# armor_schematic_std_single.net
KiCad netlist of a schematic drawn in EasyEDA
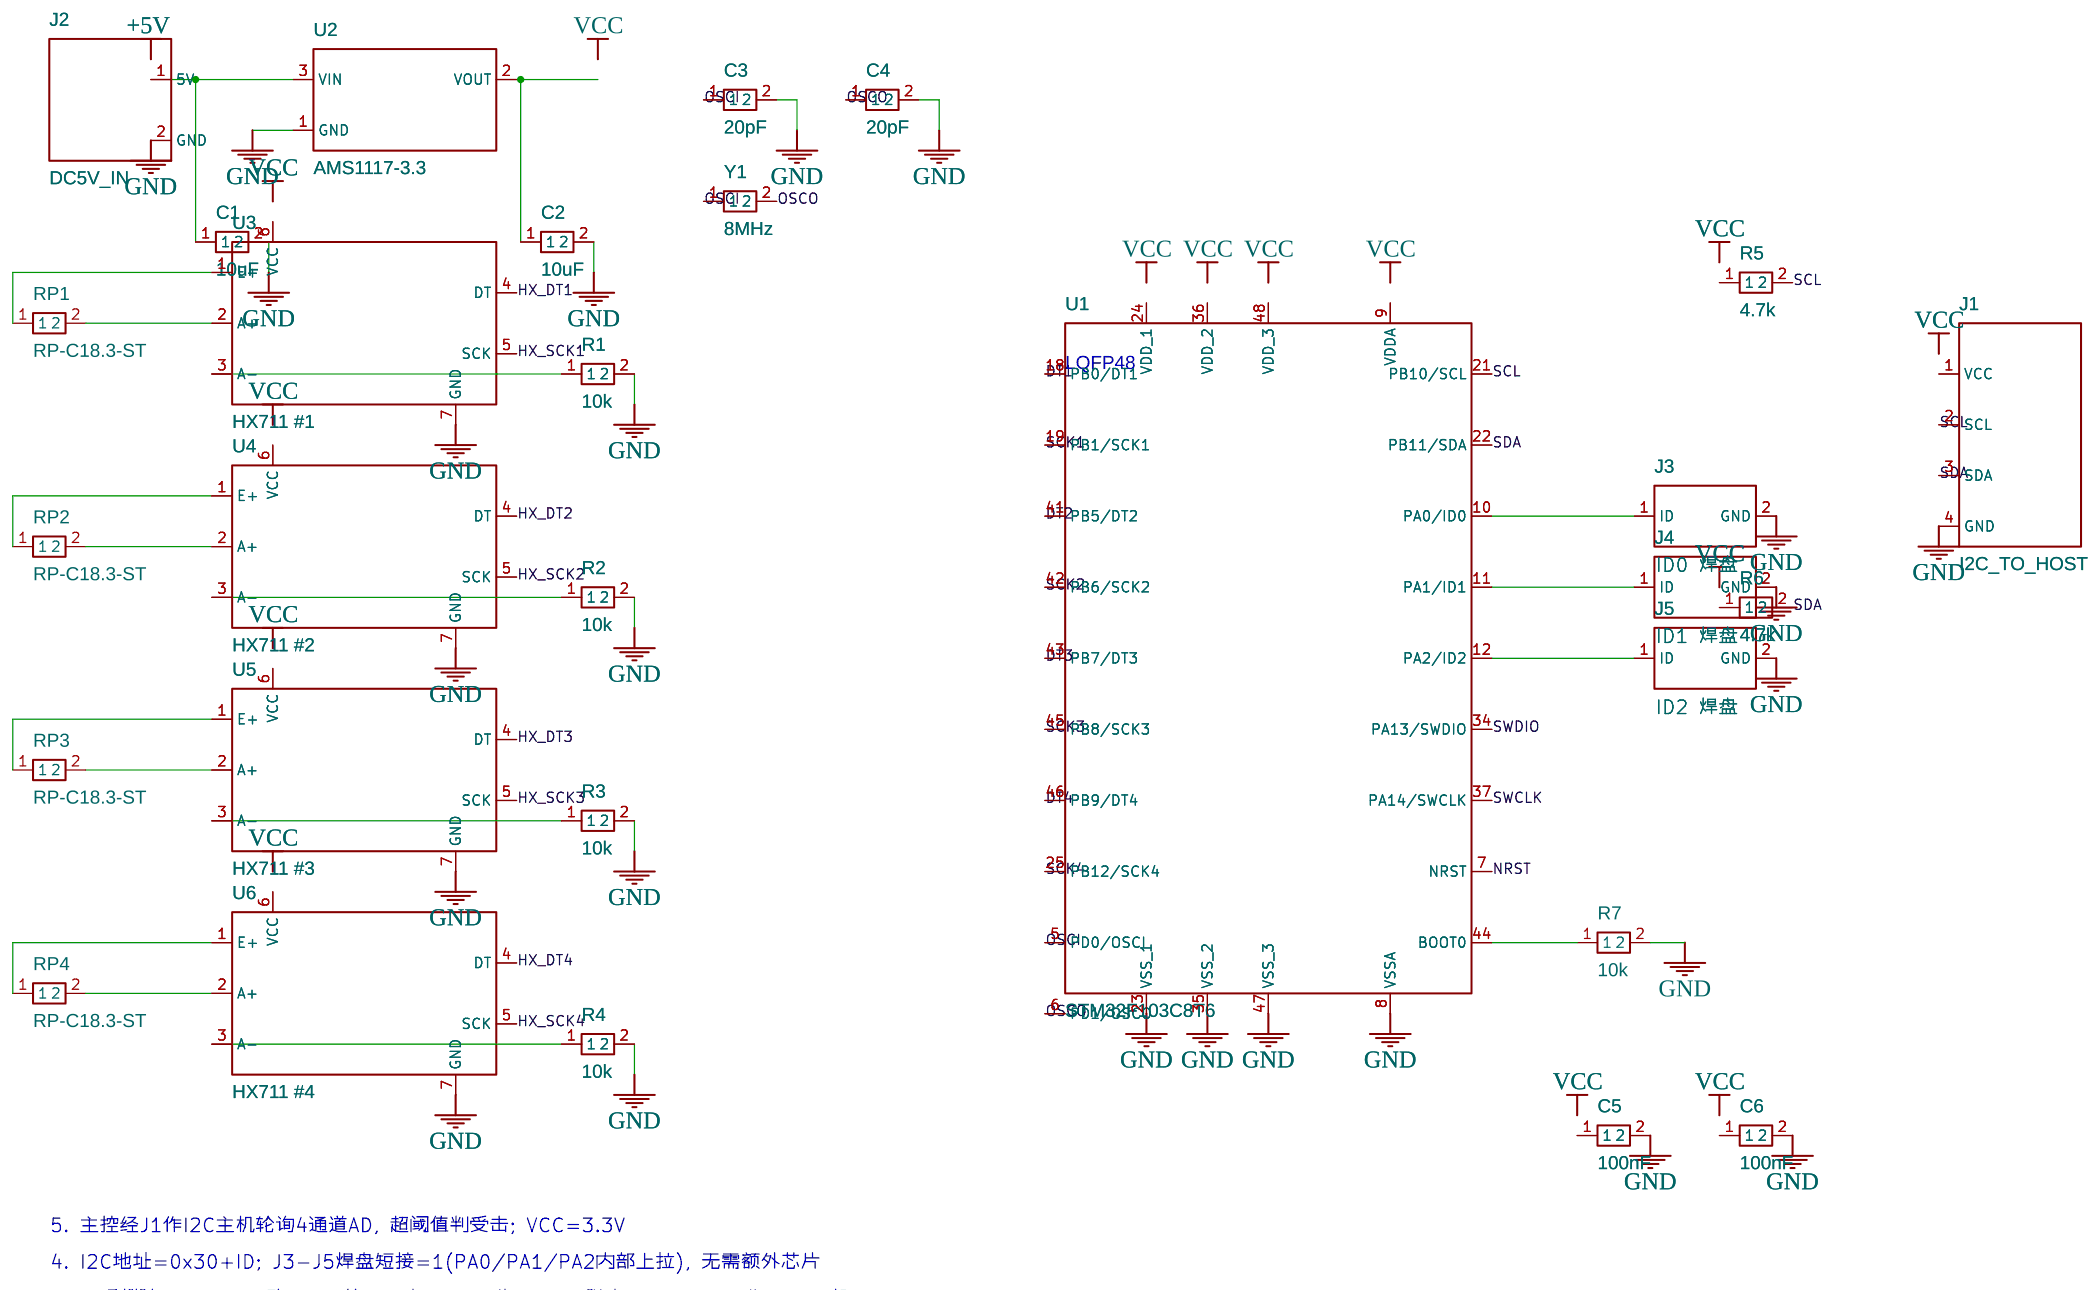
[diagram p0: schematic sheet]

(export (version "E")
  (design (tool "Eeschema 10.0.6"))
  (components
    (comp (ref "C1")
      (value "10uF")
      (fields (field (name "BOM_Manufacturer Part") "CL21A106KAYNNNE"))
      (libsource (lib "") (part "10uF"))
    )
    (comp (ref "C2")
      (value "10uF")
      (fields (field (name "BOM_Manufacturer Part") "CL21A106KAYNNNE"))
      (libsource (lib "") (part "10uF"))
    )
    (comp (ref "C3")
      (value "20pF")
      (fields (field (name "BOM_Manufacturer Part") "CL10C200JB8NNNC"))
      (libsource (lib "") (part "20pF"))
    )
    (comp (ref "C4")
      (value "20pF")
      (fields (field (name "BOM_Manufacturer Part") "CL10C200JB8NNNC"))
      (libsource (lib "") (part "20pF"))
    )
    (comp (ref "C5")
      (value "100nF")
      (fields (field (name "BOM_Manufacturer Part") "CC0603KRX7R9BB104"))
      (libsource (lib "") (part "100nF"))
    )
    (comp (ref "C6")
      (value "100nF")
      (fields (field (name "BOM_Manufacturer Part") "CC0603KRX7R9BB104"))
      (libsource (lib "") (part "100nF"))
    )
    (comp (ref "J1")
      (value "I2C_TO_HOST")
      (fields (field (name "BOM_Manufacturer Part") "PZ254V-11-04P"))
      (libsource (lib "") (part "I2C_TO_HOST"))
    )
    (comp (ref "J2")
      (value "DC5V_IN")
      (fields (field (name "BOM_Manufacturer Part") "PZ254V-11-02P"))
      (libsource (lib "") (part "DC5V_IN"))
    )
    (comp (ref "J3")
      (value "ID0 焊盘")
      (fields (field (name "BOM_Manufacturer Part") "PZ254V-11-02P"))
      (libsource (lib "") (part "ID0 焊盘"))
    )
    (comp (ref "J4")
      (value "ID1 焊盘")
      (fields (field (name "BOM_Manufacturer Part") "PZ254V-11-02P"))
      (libsource (lib "") (part "ID1 焊盘"))
    )
    (comp (ref "J5")
      (value "ID2 焊盘")
      (fields (field (name "BOM_Manufacturer Part") "PZ254V-11-02P"))
      (libsource (lib "") (part "ID2 焊盘"))
    )
    (comp (ref "R1")
      (value "10k")
      (fields (field (name "BOM_Manufacturer Part") "0603WAF1002T5E"))
      (libsource (lib "") (part "10k"))
    )
    (comp (ref "R2")
      (value "10k")
      (fields (field (name "BOM_Manufacturer Part") "0603WAF1002T5E"))
      (libsource (lib "") (part "10k"))
    )
    (comp (ref "R3")
      (value "10k")
      (fields (field (name "BOM_Manufacturer Part") "0603WAF1002T5E"))
      (libsource (lib "") (part "10k"))
    )
    (comp (ref "R4")
      (value "10k")
      (fields (field (name "BOM_Manufacturer Part") "0603WAF1002T5E"))
      (libsource (lib "") (part "10k"))
    )
    (comp (ref "R5")
      (value "4.7k")
      (fields (field (name "BOM_Manufacturer Part") "0603WAF4701T5E"))
      (libsource (lib "") (part "4.7k"))
    )
    (comp (ref "R6")
      (value "4.7k")
      (fields (field (name "BOM_Manufacturer Part") "0603WAF4701T5E"))
      (libsource (lib "") (part "4.7k"))
    )
    (comp (ref "R7")
      (value "10k")
      (fields (field (name "BOM_Manufacturer Part") "0603WAF1002T5E"))
      (libsource (lib "") (part "10k"))
    )
    (comp (ref "RP1") (value "RP-C18.3-ST") (libsource (lib "") (part "RP-C18.3-ST")))
    (comp (ref "RP2") (value "RP-C18.3-ST") (libsource (lib "") (part "RP-C18.3-ST")))
    (comp (ref "RP3") (value "RP-C18.3-ST") (libsource (lib "") (part "RP-C18.3-ST")))
    (comp (ref "RP4") (value "RP-C18.3-ST") (libsource (lib "") (part "RP-C18.3-ST")))
    (comp (ref "U1") (value "STM32F103C8T6") (libsource (lib "") (part "STM32F103C8T6")))
    (comp (ref "U2") (value "AMS1117-3.3") (libsource (lib "") (part "AMS1117-3.3")))
    (comp (ref "U3")
      (value "HX711 #1")
      (fields (field (name "BOM_Manufacturer Part") "HX711 module"))
      (libsource (lib "") (part "HX711 #1"))
    )
    (comp (ref "U4")
      (value "HX711 #2")
      (fields (field (name "BOM_Manufacturer Part") "HX711 module"))
      (libsource (lib "") (part "HX711 #2"))
    )
    (comp (ref "U5")
      (value "HX711 #3")
      (fields (field (name "BOM_Manufacturer Part") "HX711 module"))
      (libsource (lib "") (part "HX711 #3"))
    )
    (comp (ref "U6")
      (value "HX711 #4")
      (fields (field (name "BOM_Manufacturer Part") "HX711 module"))
      (libsource (lib "") (part "HX711 #4"))
    )
    (comp (ref "Y1")
      (value "8MHz")
      (fields (field (name "BOM_Manufacturer Part") "7U08000E10UCG"))
      (libsource (lib "") (part "8MHz"))
    )
  )
  (nets
    (net (code "2") (name "/DT1") (class "Default")
      (node (ref "U1") (pin "18") (pinfunction "PB0/DT1_18") (pintype "unspecified"))
    )
    (net (code "3") (name "/DT2") (class "Default")
      (node (ref "U1") (pin "41") (pinfunction "PB5/DT2_41") (pintype "unspecified"))
    )
    (net (code "4") (name "/DT3") (class "Default")
      (node (ref "U1") (pin "43") (pinfunction "PB7/DT3_43") (pintype "unspecified"))
    )
    (net (code "5") (name "/DT4") (class "Default")
      (node (ref "U1") (pin "46") (pinfunction "PB9/DT4_46") (pintype "unspecified"))
    )
    (net (code "6") (name "/HX_DT1") (class "Default")
      (node (ref "U3") (pin "4") (pinfunction "DT_4") (pintype "unspecified"))
    )
    (net (code "7") (name "/HX_DT2") (class "Default")
      (node (ref "U4") (pin "4") (pinfunction "DT_4") (pintype "unspecified"))
    )
    (net (code "8") (name "/HX_DT3") (class "Default")
      (node (ref "U5") (pin "4") (pinfunction "DT_4") (pintype "unspecified"))
    )
    (net (code "9") (name "/HX_DT4") (class "Default")
      (node (ref "U6") (pin "4") (pinfunction "DT_4") (pintype "unspecified"))
    )
    (net (code "10") (name "/HX_SCK1") (class "Default")
      (node (ref "U3") (pin "5") (pinfunction "SCK_5") (pintype "unspecified"))
    )
    (net (code "11") (name "/HX_SCK2") (class "Default")
      (node (ref "U4") (pin "5") (pinfunction "SCK_5") (pintype "unspecified"))
    )
    (net (code "12") (name "/HX_SCK3") (class "Default")
      (node (ref "U5") (pin "5") (pinfunction "SCK_5") (pintype "unspecified"))
    )
    (net (code "13") (name "/HX_SCK4") (class "Default")
      (node (ref "U6") (pin "5") (pinfunction "SCK_5") (pintype "unspecified"))
    )
    (net (code "14") (name "/NRST") (class "Default")
      (node (ref "U1") (pin "7") (pinfunction "NRST_7") (pintype "unspecified"))
    )
    (net (code "15") (name "/OSCI") (class "Default")
      (node (ref "C3") (pin "1") (pinfunction "1_1") (pintype "unspecified"))
      (node (ref "U1") (pin "5") (pinfunction "PD0/OSCI_5") (pintype "unspecified"))
      (node (ref "Y1") (pin "1") (pinfunction "1_1") (pintype "unspecified"))
    )
    (net (code "16") (name "/OSCO") (class "Default")
      (node (ref "C4") (pin "1") (pinfunction "1_1") (pintype "unspecified"))
      (node (ref "U1") (pin "6") (pinfunction "PD1/OSCO_6") (pintype "unspecified"))
      (node (ref "Y1") (pin "2") (pinfunction "2_2") (pintype "unspecified"))
    )
    (net (code "17") (name "/SCK1") (class "Default")
      (node (ref "U1") (pin "19") (pinfunction "PB1/SCK1_19") (pintype "unspecified"))
    )
    (net (code "18") (name "/SCK2") (class "Default")
      (node (ref "U1") (pin "42") (pinfunction "PB6/SCK2_42") (pintype "unspecified"))
    )
    (net (code "19") (name "/SCK3") (class "Default")
      (node (ref "U1") (pin "45") (pinfunction "PB8/SCK3_45") (pintype "unspecified"))
    )
    (net (code "20") (name "/SCK4") (class "Default")
      (node (ref "U1") (pin "25") (pinfunction "PB12/SCK4_25") (pintype "unspecified"))
    )
    (net (code "21") (name "/SCL") (class "Default")
      (node (ref "J1") (pin "2") (pinfunction "SCL_2") (pintype "unspecified"))
      (node (ref "R5") (pin "2") (pinfunction "2_2") (pintype "unspecified"))
      (node (ref "U1") (pin "21") (pinfunction "PB10/SCL_21") (pintype "unspecified"))
    )
    (net (code "22") (name "/SDA") (class "Default")
      (node (ref "J1") (pin "3") (pinfunction "SDA_3") (pintype "unspecified"))
      (node (ref "R6") (pin "2") (pinfunction "2_2") (pintype "unspecified"))
      (node (ref "U1") (pin "22") (pinfunction "PB11/SDA_22") (pintype "unspecified"))
    )
    (net (code "23") (name "/SWCLK") (class "Default")
      (node (ref "U1") (pin "37") (pinfunction "PA14/SWCLK_37") (pintype "unspecified"))
    )
    (net (code "24") (name "/SWDIO") (class "Default")
      (node (ref "U1") (pin "34") (pinfunction "PA13/SWDIO_34") (pintype "unspecified"))
    )
    (net (code "25") (name "GND") (class "Default")
      (node (ref "C1") (pin "2") (pinfunction "2_2") (pintype "unspecified"))
      (node (ref "C2") (pin "2") (pinfunction "2_2") (pintype "unspecified"))
      (node (ref "C3") (pin "2") (pinfunction "2_2") (pintype "unspecified"))
      (node (ref "C4") (pin "2") (pinfunction "2_2") (pintype "unspecified"))
      (node (ref "C5") (pin "2") (pinfunction "2_2") (pintype "unspecified"))
      (node (ref "C6") (pin "2") (pinfunction "2_2") (pintype "unspecified"))
      (node (ref "J1") (pin "4") (pinfunction "GND_4") (pintype "unspecified"))
      (node (ref "J2") (pin "2") (pinfunction "GND_2") (pintype "unspecified"))
      (node (ref "J3") (pin "2") (pinfunction "GND_2") (pintype "unspecified"))
      (node (ref "J4") (pin "2") (pinfunction "GND_2") (pintype "unspecified"))
      (node (ref "J5") (pin "2") (pinfunction "GND_2") (pintype "unspecified"))
      (node (ref "R1") (pin "2") (pinfunction "2_2") (pintype "unspecified"))
      (node (ref "R2") (pin "2") (pinfunction "2_2") (pintype "unspecified"))
      (node (ref "R3") (pin "2") (pinfunction "2_2") (pintype "unspecified"))
      (node (ref "R4") (pin "2") (pinfunction "2_2") (pintype "unspecified"))
      (node (ref "R7") (pin "2") (pinfunction "2_2") (pintype "unspecified"))
      (node (ref "U1") (pin "23") (pinfunction "VSS_1_23") (pintype "unspecified"))
      (node (ref "U1") (pin "35") (pinfunction "VSS_2_35") (pintype "unspecified"))
      (node (ref "U1") (pin "47") (pinfunction "VSS_3_47") (pintype "unspecified"))
      (node (ref "U1") (pin "8") (pinfunction "VSSA_8") (pintype "unspecified"))
      (node (ref "U2") (pin "1") (pinfunction "GND_1") (pintype "unspecified"))
      (node (ref "U3") (pin "7") (pinfunction "GND_7") (pintype "unspecified"))
      (node (ref "U4") (pin "7") (pinfunction "GND_7") (pintype "unspecified"))
      (node (ref "U5") (pin "7") (pinfunction "GND_7") (pintype "unspecified"))
      (node (ref "U6") (pin "7") (pinfunction "GND_7") (pintype "unspecified"))
    )
    (net (code "26") (name "Net-(J2-5V)") (class "Default")
      (node (ref "C1") (pin "1") (pinfunction "1_1") (pintype "unspecified"))
      (node (ref "J2") (pin "1") (pinfunction "5V_1") (pintype "unspecified"))
      (node (ref "U2") (pin "3") (pinfunction "VIN_3") (pintype "unspecified"))
    )
    (net (code "27") (name "Net-(J3-ID)") (class "Default")
      (node (ref "J3") (pin "1") (pinfunction "ID_1") (pintype "unspecified"))
      (node (ref "U1") (pin "10") (pinfunction "PA0/ID0_10") (pintype "unspecified"))
    )
    (net (code "28") (name "Net-(J4-ID)") (class "Default")
      (node (ref "J4") (pin "1") (pinfunction "ID_1") (pintype "unspecified"))
      (node (ref "U1") (pin "11") (pinfunction "PA1/ID1_11") (pintype "unspecified"))
    )
    (net (code "29") (name "Net-(J5-ID)") (class "Default")
      (node (ref "J5") (pin "1") (pinfunction "ID_1") (pintype "unspecified"))
      (node (ref "U1") (pin "12") (pinfunction "PA2/ID2_12") (pintype "unspecified"))
    )
    (net (code "30") (name "Net-(U1-BOOT0)") (class "Default")
      (node (ref "R7") (pin "1") (pinfunction "1_1") (pintype "unspecified"))
      (node (ref "U1") (pin "44") (pinfunction "BOOT0_44") (pintype "unspecified"))
    )
    (net (code "31") (name "Net-(U2-VOUT)") (class "Default")
      (node (ref "C2") (pin "1") (pinfunction "1_1") (pintype "unspecified"))
      (node (ref "U2") (pin "2") (pinfunction "VOUT_2") (pintype "unspecified"))
    )
    (net (code "32") (name "Net-(U3-A+)") (class "Default")
      (node (ref "RP1") (pin "2") (pinfunction "2_2") (pintype "unspecified"))
      (node (ref "U3") (pin "2") (pinfunction "A+_2") (pintype "unspecified"))
    )
    (net (code "33") (name "Net-(U3-A-)") (class "Default")
      (node (ref "R1") (pin "1") (pinfunction "1_1") (pintype "unspecified"))
      (node (ref "U3") (pin "3") (pinfunction "A-_3") (pintype "unspecified"))
    )
    (net (code "34") (name "Net-(U3-E+)") (class "Default")
      (node (ref "RP1") (pin "1") (pinfunction "1_1") (pintype "unspecified"))
      (node (ref "U3") (pin "1") (pinfunction "E+_1") (pintype "unspecified"))
    )
    (net (code "35") (name "Net-(U4-A+)") (class "Default")
      (node (ref "RP2") (pin "2") (pinfunction "2_2") (pintype "unspecified"))
      (node (ref "U4") (pin "2") (pinfunction "A+_2") (pintype "unspecified"))
    )
    (net (code "36") (name "Net-(U4-A-)") (class "Default")
      (node (ref "R2") (pin "1") (pinfunction "1_1") (pintype "unspecified"))
      (node (ref "U4") (pin "3") (pinfunction "A-_3") (pintype "unspecified"))
    )
    (net (code "37") (name "Net-(U4-E+)") (class "Default")
      (node (ref "RP2") (pin "1") (pinfunction "1_1") (pintype "unspecified"))
      (node (ref "U4") (pin "1") (pinfunction "E+_1") (pintype "unspecified"))
    )
    (net (code "38") (name "Net-(U5-A+)") (class "Default")
      (node (ref "RP3") (pin "2") (pinfunction "2_2") (pintype "unspecified"))
      (node (ref "U5") (pin "2") (pinfunction "A+_2") (pintype "unspecified"))
    )
    (net (code "39") (name "Net-(U5-A-)") (class "Default")
      (node (ref "R3") (pin "1") (pinfunction "1_1") (pintype "unspecified"))
      (node (ref "U5") (pin "3") (pinfunction "A-_3") (pintype "unspecified"))
    )
    (net (code "40") (name "Net-(U5-E+)") (class "Default")
      (node (ref "RP3") (pin "1") (pinfunction "1_1") (pintype "unspecified"))
      (node (ref "U5") (pin "1") (pinfunction "E+_1") (pintype "unspecified"))
    )
    (net (code "41") (name "Net-(U6-A+)") (class "Default")
      (node (ref "RP4") (pin "2") (pinfunction "2_2") (pintype "unspecified"))
      (node (ref "U6") (pin "2") (pinfunction "A+_2") (pintype "unspecified"))
    )
    (net (code "42") (name "Net-(U6-A-)") (class "Default")
      (node (ref "R4") (pin "1") (pinfunction "1_1") (pintype "unspecified"))
      (node (ref "U6") (pin "3") (pinfunction "A-_3") (pintype "unspecified"))
    )
    (net (code "43") (name "Net-(U6-E+)") (class "Default")
      (node (ref "RP4") (pin "1") (pinfunction "1_1") (pintype "unspecified"))
      (node (ref "U6") (pin "1") (pinfunction "E+_1") (pintype "unspecified"))
    )
    (net (code "45") (name "unconnected-(C5-Pad1)") (class "Default")
      (node (ref "C5") (pin "1") (pinfunction "1_1") (pintype "unspecified"))
    )
    (net (code "46") (name "unconnected-(C6-Pad1)") (class "Default")
      (node (ref "C6") (pin "1") (pinfunction "1_1") (pintype "unspecified"))
    )
    (net (code "47") (name "unconnected-(J1-VCC-Pad1)") (class "Default")
      (node (ref "J1") (pin "1") (pinfunction "VCC_1") (pintype "unspecified"))
    )
    (net (code "48") (name "unconnected-(R5-Pad1)") (class "Default")
      (node (ref "R5") (pin "1") (pinfunction "1_1") (pintype "unspecified"))
    )
    (net (code "49") (name "unconnected-(R6-Pad1)") (class "Default")
      (node (ref "R6") (pin "1") (pinfunction "1_1") (pintype "unspecified"))
    )
    (net (code "50") (name "unconnected-(U1-VDDA-Pad9)") (class "Default")
      (node (ref "U1") (pin "9") (pinfunction "VDDA_9") (pintype "unspecified"))
    )
    (net (code "51") (name "unconnected-(U1-VDD_1-Pad24)") (class "Default")
      (node (ref "U1") (pin "24") (pinfunction "VDD_1_24") (pintype "unspecified"))
    )
    (net (code "52") (name "unconnected-(U1-VDD_2-Pad36)") (class "Default")
      (node (ref "U1") (pin "36") (pinfunction "VDD_2_36") (pintype "unspecified"))
    )
    (net (code "53") (name "unconnected-(U1-VDD_3-Pad48)") (class "Default")
      (node (ref "U1") (pin "48") (pinfunction "VDD_3_48") (pintype "unspecified"))
    )
    (net (code "54") (name "unconnected-(U3-VCC-Pad6)") (class "Default")
      (node (ref "U3") (pin "6") (pinfunction "VCC_6") (pintype "unspecified"))
    )
    (net (code "55") (name "unconnected-(U4-VCC-Pad6)") (class "Default")
      (node (ref "U4") (pin "6") (pinfunction "VCC_6") (pintype "unspecified"))
    )
    (net (code "56") (name "unconnected-(U5-VCC-Pad6)") (class "Default")
      (node (ref "U5") (pin "6") (pinfunction "VCC_6") (pintype "unspecified"))
    )
    (net (code "57") (name "unconnected-(U6-VCC-Pad6)") (class "Default")
      (node (ref "U6") (pin "6") (pinfunction "VCC_6") (pintype "unspecified"))
    )
  )
)
